# 23D_ESC_DRIVER.net
KiCad netlist of a schematic drawn in Altium Designer
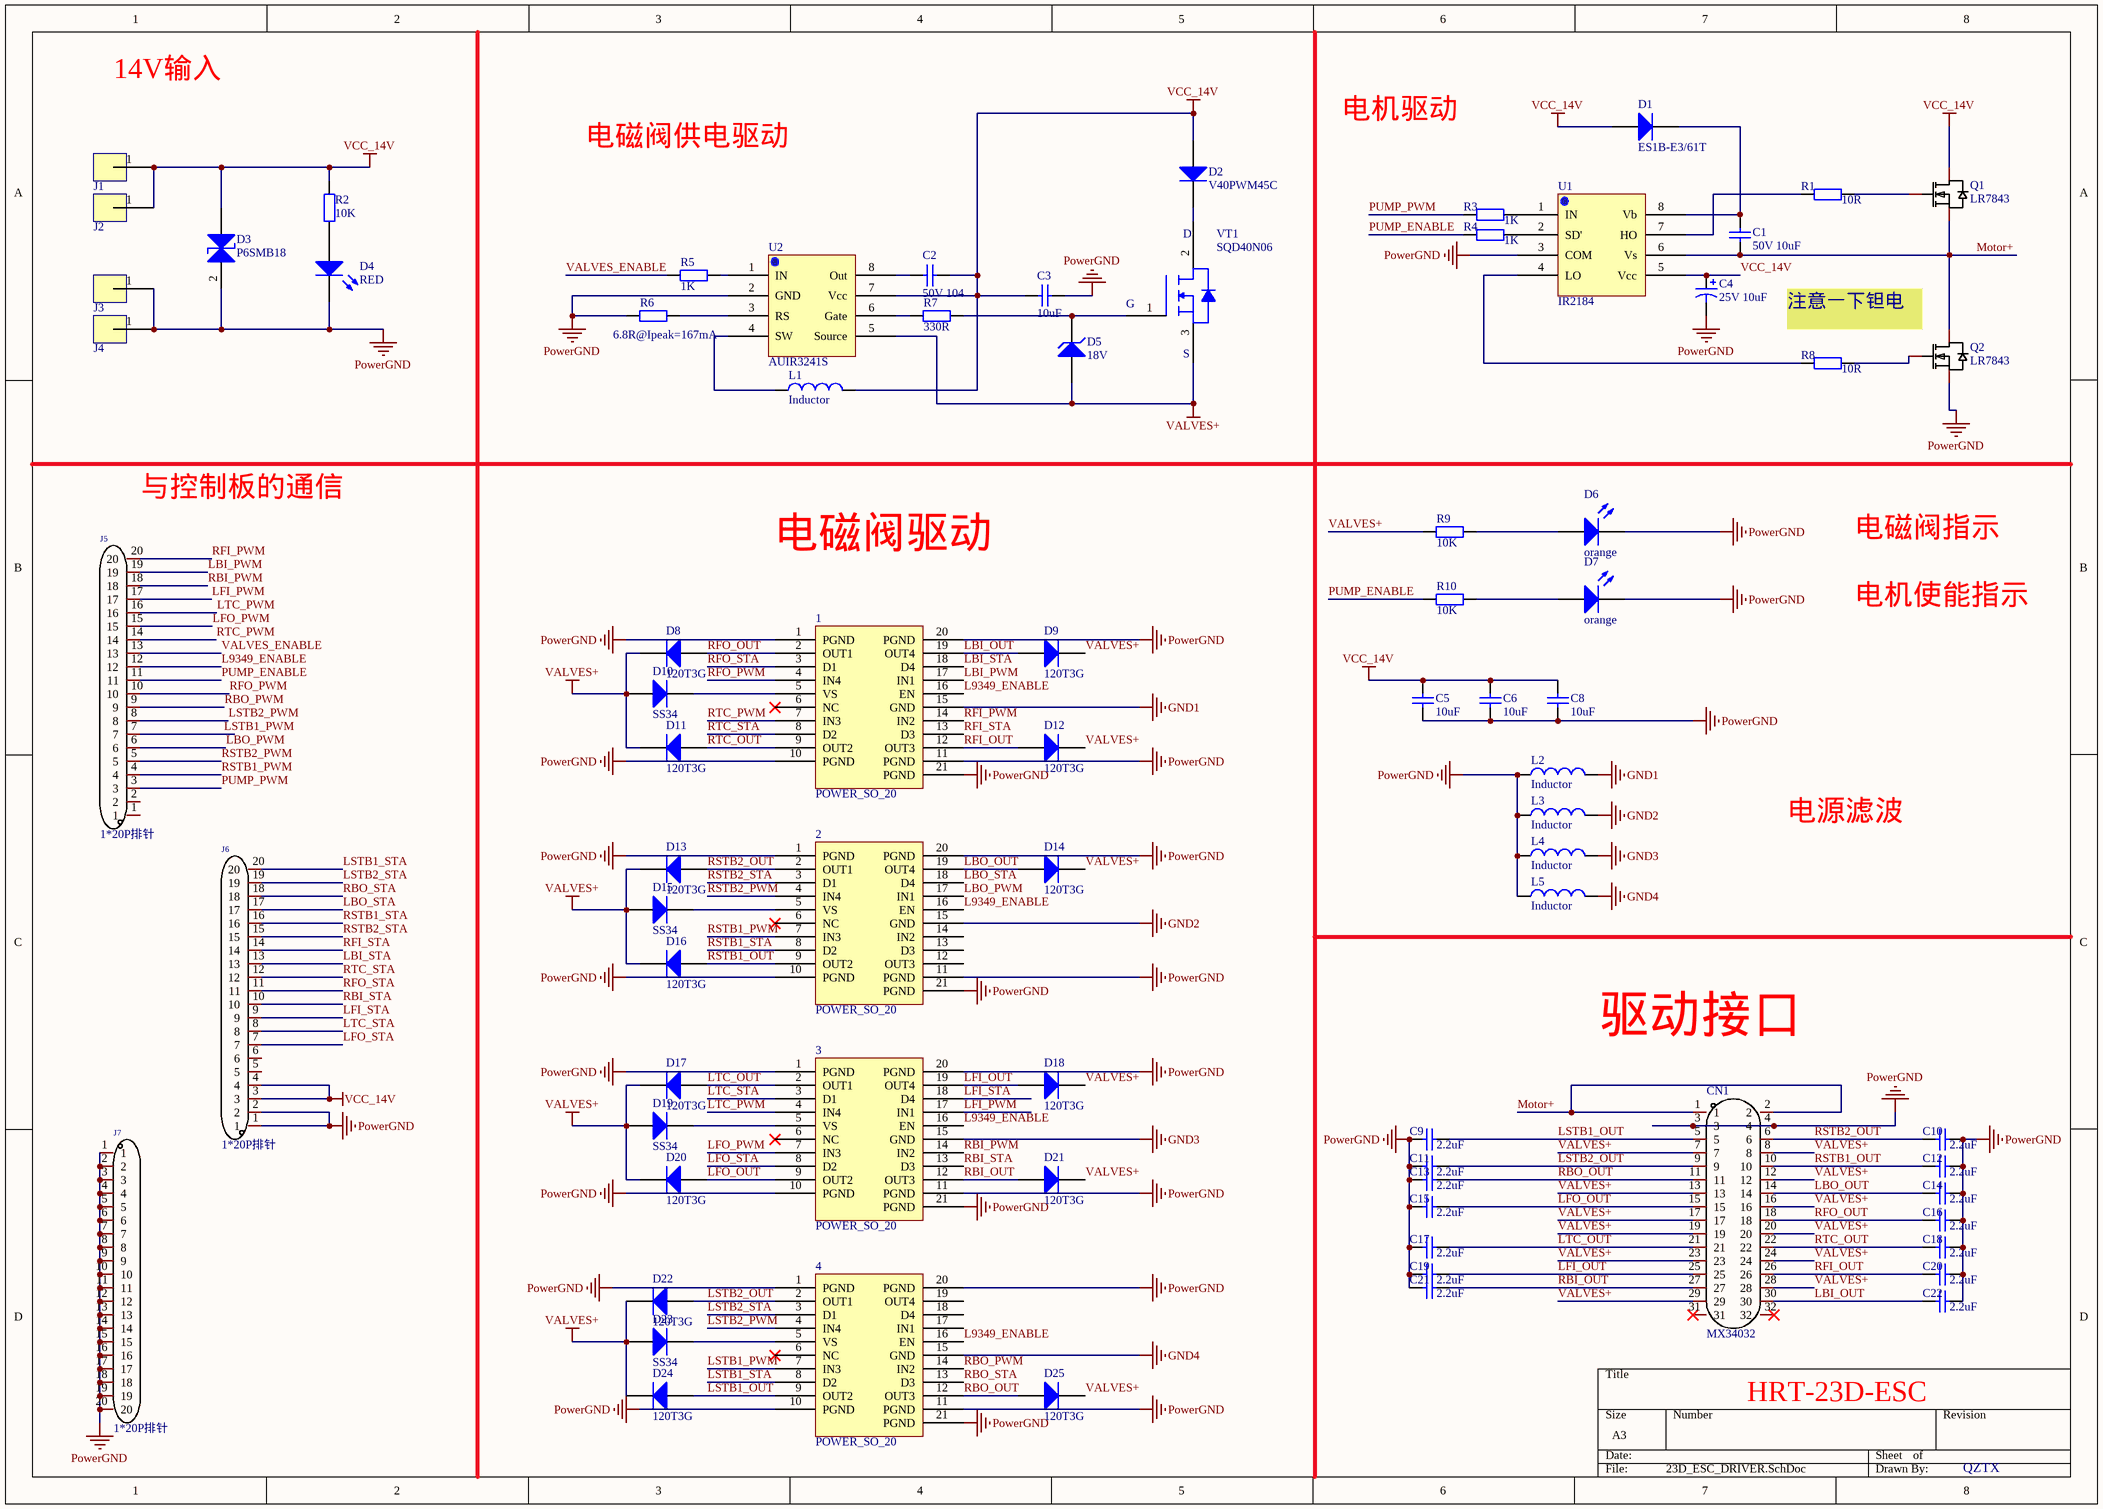
[diagram p0: 23D_ESC_DRIVER.SchDoc]

(export (version "E")
  (design (tool "Eeschema 10.0.6"))
  (components
    (comp (ref "1")
      (value "POWER_SO_20")
      (footprint "POWERSO-20_self_with3D_USEable:POWERSO-20_L15.9-W11.0-P1.27-LS14.2-BL-EP")
      (libsource (lib "PowerSO-20") (part "POWER_SO_20"))
    )
    (comp (ref "2")
      (value "POWER_SO_20")
      (footprint "POWERSO-20_self_with3D_USEable:POWERSO-20_L15.9-W11.0-P1.27-LS14.2-BL-EP")
      (libsource (lib "PowerSO-20") (part "POWER_SO_20"))
    )
    (comp (ref "3")
      (value "POWER_SO_20")
      (footprint "POWERSO-20_self_with3D_USEable:POWERSO-20_L15.9-W11.0-P1.27-LS14.2-BL-EP")
      (libsource (lib "PowerSO-20") (part "POWER_SO_20"))
    )
    (comp (ref "4")
      (value "POWER_SO_20")
      (footprint "POWERSO-20_self_with3D_USEable:POWERSO-20_L15.9-W11.0-P1.27-LS14.2-BL-EP")
      (libsource (lib "PowerSO-20") (part "POWER_SO_20"))
    )
    (comp (ref "C1")
      (value "50V 10uF")
      (footprint "C 0805")
      (description "无极性电容")
      (libsource (lib "HRT_D Schlib") (part "Cap"))
    )
    (comp (ref "C2")
      (value "50V 104")
      (footprint "C 0805")
      (description "无极性电容")
      (libsource (lib "HRT_D Schlib") (part "Cap"))
    )
    (comp (ref "C3")
      (value "10uF")
      (footprint "C 0805")
      (description "无极性电容")
      (libsource (lib "HRT_D Schlib") (part "Cap"))
    )
    (comp (ref "C4")
      (value "25V 10uF")
      (footprint "CP 3528B")
      (description "极性电容")
      (libsource (lib "ER100_ESC") (part "Cap_Pol"))
    )
    (comp (ref "C5")
      (value "10uF")
      (footprint "C 0805")
      (description "无极性电容")
      (libsource (lib "HRT_D Schlib") (part "Cap"))
    )
    (comp (ref "C6")
      (value "10uF")
      (footprint "C 0805")
      (description "无极性电容")
      (libsource (lib "HRT_D Schlib") (part "Cap"))
    )
    (comp (ref "C8")
      (value "10uF")
      (footprint "C 0805")
      (description "无极性电容")
      (libsource (lib "HRT_D Schlib") (part "Cap"))
    )
    (comp (ref "C9")
      (value "2.2uF")
      (footprint "C 0805")
      (description "无极性电容")
      (libsource (lib "HRT_D Schlib") (part "Cap"))
    )
    (comp (ref "C10")
      (value "2.2uF")
      (footprint "C 0805")
      (description "无极性电容")
      (libsource (lib "HRT_D Schlib") (part "Cap"))
    )
    (comp (ref "C11")
      (value "2.2uF")
      (footprint "C 0805")
      (description "无极性电容")
      (libsource (lib "HRT_D Schlib") (part "Cap"))
    )
    (comp (ref "C12")
      (value "2.2uF")
      (footprint "C 0805")
      (description "无极性电容")
      (libsource (lib "HRT_D Schlib") (part "Cap"))
    )
    (comp (ref "C13")
      (value "2.2uF")
      (footprint "C 0805")
      (description "无极性电容")
      (libsource (lib "HRT_D Schlib") (part "Cap"))
    )
    (comp (ref "C14")
      (value "2.2uF")
      (footprint "C 0805")
      (description "无极性电容")
      (libsource (lib "HRT_D Schlib") (part "Cap"))
    )
    (comp (ref "C15")
      (value "2.2uF")
      (footprint "C 0805")
      (description "无极性电容")
      (libsource (lib "HRT_D Schlib") (part "Cap"))
    )
    (comp (ref "C16")
      (value "2.2uF")
      (footprint "C 0805")
      (description "无极性电容")
      (libsource (lib "HRT_D Schlib") (part "Cap"))
    )
    (comp (ref "C17")
      (value "2.2uF")
      (footprint "C 0805")
      (description "无极性电容")
      (libsource (lib "HRT_D Schlib") (part "Cap"))
    )
    (comp (ref "C18")
      (value "2.2uF")
      (footprint "C 0805")
      (description "无极性电容")
      (libsource (lib "HRT_D Schlib") (part "Cap"))
    )
    (comp (ref "C19")
      (value "2.2uF")
      (footprint "C 0805")
      (description "无极性电容")
      (libsource (lib "HRT_D Schlib") (part "Cap"))
    )
    (comp (ref "C20")
      (value "2.2uF")
      (footprint "C 0805")
      (description "无极性电容")
      (libsource (lib "HRT_D Schlib") (part "Cap"))
    )
    (comp (ref "C21")
      (value "2.2uF")
      (footprint "C 0805")
      (description "无极性电容")
      (libsource (lib "HRT_D Schlib") (part "Cap"))
    )
    (comp (ref "C22")
      (value "2.2uF")
      (footprint "C 0805")
      (description "无极性电容")
      (libsource (lib "HRT_D Schlib") (part "Cap"))
    )
    (comp (ref "CN1")
      (value "MX34032NF2")
      (footprint "CONN-TH_MX34032NF2")
      (description "间距:2.2mm;插针结构:2x16P;排数:2;每排PIN数:16;行距:3mm;公母:公型插针;安装方式:弯插;")
      (fields (field (name "MANUFACTURER") "JAE(日本航空电子)") (field (name "NAME") "MX34032"))
      (libsource (lib "MX34032") (part "MX34032NF2"))
    )
    (comp (ref "D1")
      (value "ES1B-E3/61T")
      (footprint "DO-214")
      (description "二极管")
      (libsource (lib "ER100_ESC") (part "Diode"))
    )
    (comp (ref "D2")
      (value "V40PWM45C")
      (footprint "TO252_DIO")
      (description "二极管")
      (libsource (lib "ER100_ESC") (part "Diode"))
    )
    (comp (ref "D3")
      (value "P6SMB18")
      (footprint "DO-214AA")
      (description "BiDir TVS Diode")
      (libsource (lib "ER100_ESC") (part "P6SMBXX"))
    )
    (comp (ref "D4")
      (value "RED")
      (footprint "LED_0805")
      (description "发光二极管")
      (libsource (lib "ESC_control") (part "LED"))
    )
    (comp (ref "D5") (value "18V") (footprint "LL34") (libsource (lib "ER100_ESC") (part "Diode_Zener")))
    (comp (ref "D6")
      (value "orange")
      (footprint "LED_0805")
      (description "发光二极管")
      (libsource (lib "ESC_control") (part "LED"))
    )
    (comp (ref "D7")
      (value "orange")
      (footprint "LED_0805")
      (description "发光二极管")
      (libsource (lib "ESC_control") (part "LED"))
    )
    (comp (ref "D8")
      (value "120T3G")
      (footprint "DO-214")
      (description "二极管")
      (libsource (lib "ER100_ESC") (part "Diode"))
    )
    (comp (ref "D9")
      (value "120T3G")
      (footprint "DO-214")
      (description "二极管")
      (libsource (lib "ER100_ESC") (part "Diode"))
    )
    (comp (ref "D10")
      (value "SS34")
      (footprint "DO-214")
      (description "二极管")
      (libsource (lib "ESC_control") (part "Diode"))
    )
    (comp (ref "D11")
      (value "120T3G")
      (footprint "DO-214")
      (description "二极管")
      (libsource (lib "ER100_ESC") (part "Diode"))
    )
    (comp (ref "D12")
      (value "120T3G")
      (footprint "DO-214")
      (description "二极管")
      (libsource (lib "ER100_ESC") (part "Diode"))
    )
    (comp (ref "D13")
      (value "120T3G")
      (footprint "DO-214")
      (description "二极管")
      (libsource (lib "ER100_ESC") (part "Diode"))
    )
    (comp (ref "D14")
      (value "120T3G")
      (footprint "DO-214")
      (description "二极管")
      (libsource (lib "ER100_ESC") (part "Diode"))
    )
    (comp (ref "D15")
      (value "SS34")
      (footprint "DO-214")
      (description "二极管")
      (libsource (lib "ESC_control") (part "Diode"))
    )
    (comp (ref "D16")
      (value "120T3G")
      (footprint "DO-214")
      (description "二极管")
      (libsource (lib "ER100_ESC") (part "Diode"))
    )
    (comp (ref "D17")
      (value "120T3G")
      (footprint "DO-214")
      (description "二极管")
      (libsource (lib "ER100_ESC") (part "Diode"))
    )
    (comp (ref "D18")
      (value "120T3G")
      (footprint "DO-214")
      (description "二极管")
      (libsource (lib "ER100_ESC") (part "Diode"))
    )
    (comp (ref "D19")
      (value "SS34")
      (footprint "DO-214")
      (description "二极管")
      (libsource (lib "ESC_control") (part "Diode"))
    )
    (comp (ref "D20")
      (value "120T3G")
      (footprint "DO-214")
      (description "二极管")
      (libsource (lib "ER100_ESC") (part "Diode"))
    )
    (comp (ref "D21")
      (value "120T3G")
      (footprint "DO-214")
      (description "二极管")
      (libsource (lib "ER100_ESC") (part "Diode"))
    )
    (comp (ref "D22")
      (value "120T3G")
      (footprint "DO-214")
      (description "二极管")
      (libsource (lib "ER100_ESC") (part "Diode"))
    )
    (comp (ref "D23")
      (value "SS34")
      (footprint "DO-214")
      (description "二极管")
      (libsource (lib "ESC_control") (part "Diode"))
    )
    (comp (ref "D24")
      (value "120T3G")
      (footprint "DO-214")
      (description "二极管")
      (libsource (lib "ER100_ESC") (part "Diode"))
    )
    (comp (ref "D25")
      (value "120T3G")
      (footprint "DO-214")
      (description "二极管")
      (libsource (lib "ER100_ESC") (part "Diode"))
    )
    (comp (ref "J1")
      (value "SMT_Connector")
      (footprint "SMT_Connector")
      (description "表贴接线端")
      (libsource (lib "ER100_ESC") (part "SMT_Connector"))
    )
    (comp (ref "J2")
      (value "SMT_Connector")
      (footprint "SMT_Connector")
      (description "表贴接线端")
      (libsource (lib "ER100_ESC") (part "SMT_Connector"))
    )
    (comp (ref "J3")
      (value "SMT_Connector")
      (footprint "SMT_Connector")
      (description "表贴接线端")
      (libsource (lib "ER100_ESC") (part "SMT_Connector"))
    )
    (comp (ref "J4")
      (value "SMT_Connector")
      (footprint "SMT_Connector")
      (description "表贴接线端")
      (libsource (lib "ER100_ESC") (part "SMT_Connector"))
    )
    (comp (ref "J5")
      (value "2.54-1*20P直针")
      (footprint "HDR-TH_20P-P2.54-V-M-1")
      (fields (field (name "MANUFACTURER") "BOOMELE(博穆精密)") (field (name "NAME") "1*20P排针"))
      (libsource (lib "20P排针2.54mm") (part "2.54-1*20P直针"))
    )
    (comp (ref "J6")
      (value "2.54-1*20P直针")
      (footprint "HDR-TH_20P-P2.54-V-M-1")
      (fields (field (name "MANUFACTURER") "BOOMELE(博穆精密)") (field (name "NAME") "1*20P排针"))
      (libsource (lib "20P排针2.54mm") (part "2.54-1*20P直针"))
    )
    (comp (ref "J7")
      (value "2.54-1*20P直针")
      (footprint "HDR2.54-LI-20P")
      (fields (field (name "MANUFACTURER") "BOOMELE(博穆精密)") (field (name "NAME") "1*20P排针"))
      (libsource (lib "20P排针2.54mm") (part "2.54-1*20P直针"))
    )
    (comp (ref "L1")
      (value "Inductor")
      (footprint "L 0805")
      (description "电感")
      (libsource (lib "HRT_D Schlib") (part "Inductor"))
    )
    (comp (ref "L2")
      (value "Inductor")
      (footprint "L 0805")
      (description "电感")
      (libsource (lib "HRT_D Schlib") (part "Inductor"))
    )
    (comp (ref "L3")
      (value "Inductor")
      (footprint "L 0805")
      (description "电感")
      (libsource (lib "HRT_D Schlib") (part "Inductor"))
    )
    (comp (ref "L4")
      (value "Inductor")
      (footprint "L 0805")
      (description "电感")
      (libsource (lib "HRT_D Schlib") (part "Inductor"))
    )
    (comp (ref "L5")
      (value "Inductor")
      (footprint "L 0805")
      (description "电感")
      (libsource (lib "HRT_D Schlib") (part "Inductor"))
    )
    (comp (ref "Q1")
      (value "LR7843-VB")
      (footprint "TO-252-2_L6.6-W6.1-P4.58-LS9.9-BR")
      (description "类型:N沟道;漏源电压(Vdss):30V;连续漏极电流(Id):120A;导通电阻(RDS(on)@Vgs,Id):2.3mΩ@10V,120A;")
      (fields (field (name "MANUFACTURER") "VBsemi(微碧)") (field (name "NAME") "LR7843"))
      (libsource (lib "LR7843") (part "LR7843-VB"))
    )
    (comp (ref "Q2")
      (value "LR7843-VB")
      (footprint "TO-252-2_L6.6-W6.1-P4.58-LS9.9-BR")
      (description "类型:N沟道;漏源电压(Vdss):30V;连续漏极电流(Id):120A;导通电阻(RDS(on)@Vgs,Id):2.3mΩ@10V,120A;")
      (fields (field (name "MANUFACTURER") "VBsemi(微碧)") (field (name "NAME") "LR7843"))
      (libsource (lib "LR7843") (part "LR7843-VB"))
    )
    (comp (ref "R1")
      (value "10R")
      (footprint "R 0805")
      (description "电阻")
      (libsource (lib "") (part "Resistor_1"))
    )
    (comp (ref "R2")
      (value "10K")
      (footprint "R 0805")
      (description "电阻")
      (libsource (lib "HRT_D Schlib") (part "Resistor"))
    )
    (comp (ref "R3")
      (value "1K")
      (footprint "R 0805")
      (description "电阻")
      (libsource (lib "") (part "Resistor_1"))
    )
    (comp (ref "R4")
      (value "1K")
      (footprint "R 0805")
      (description "电阻")
      (libsource (lib "") (part "Resistor_1"))
    )
    (comp (ref "R5")
      (value "1K")
      (footprint "R 0805")
      (description "电阻")
      (libsource (lib "") (part "Resistor_1"))
    )
    (comp (ref "R6")
      (value "6.8R@Ipeak=167mA")
      (footprint "R 0805")
      (description "电阻")
      (libsource (lib "") (part "Resistor_1"))
    )
    (comp (ref "R7")
      (value "330R")
      (footprint "R 0805")
      (description "电阻")
      (libsource (lib "") (part "Resistor_1"))
    )
    (comp (ref "R8")
      (value "10R")
      (footprint "R 0805")
      (description "电阻")
      (libsource (lib "") (part "Resistor_1"))
    )
    (comp (ref "R9")
      (value "10K")
      (footprint "R 0805")
      (description "电阻")
      (libsource (lib "") (part "Resistor_1"))
    )
    (comp (ref "R10")
      (value "10K")
      (footprint "R 0805")
      (description "电阻")
      (libsource (lib "") (part "Resistor_1"))
    )
    (comp (ref "U1")
      (value "IR2184")
      (footprint "SOP8")
      (description "Half-Bridge Gate Driver")
      (libsource (lib "ER100_ESC") (part "IR2184"))
    )
    (comp (ref "U2")
      (value "AUIR3241S")
      (footprint "SOP8")
      (description "B2B MOSFET Driver")
      (libsource (lib "ER100_ESC") (part "AUIR3241S"))
    )
    (comp (ref "VT1")
      (value "SQD40N06")
      (footprint "TO252")
      (libsource (lib "ER100_ESC") (part "PowerMos_N"))
    )
  )
  (nets
    (net (code "1") (name "/L9349_ENABLE") (class "Default")
      (node (ref "1") (pin "16") (pinfunction "EN_16") (pintype "passive"))
      (node (ref "2") (pin "16") (pinfunction "EN_16") (pintype "passive"))
      (node (ref "3") (pin "16") (pinfunction "EN_16") (pintype "passive"))
      (node (ref "4") (pin "16") (pinfunction "EN_16") (pintype "passive"))
      (node (ref "J5") (pin "12") (pinfunction "12_12") (pintype "passive"))
    )
    (net (code "2") (name "/LBI_OUT") (class "Default")
      (node (ref "1") (pin "19") (pinfunction "OUT4_19") (pintype "passive"))
      (node (ref "C22") (pin "1") (pinfunction "1_1") (pintype "passive"))
      (node (ref "CN1") (pin "30") (pinfunction "30_30") (pintype "passive"))
      (node (ref "D9") (pin "1") (pinfunction "A_1") (pintype "passive"))
    )
    (net (code "3") (name "/LBI_PWM") (class "Default")
      (node (ref "1") (pin "17") (pinfunction "IN1_17") (pintype "passive"))
      (node (ref "J5") (pin "19") (pinfunction "19_19") (pintype "passive"))
    )
    (net (code "4") (name "/LBI_STA") (class "Default")
      (node (ref "1") (pin "18") (pinfunction "D4_18") (pintype "passive"))
      (node (ref "J6") (pin "13") (pinfunction "13_13") (pintype "passive"))
    )
    (net (code "5") (name "/LBO_OUT") (class "Default")
      (node (ref "2") (pin "19") (pinfunction "OUT4_19") (pintype "passive"))
      (node (ref "C14") (pin "1") (pinfunction "1_1") (pintype "passive"))
      (node (ref "CN1") (pin "14") (pinfunction "14_14") (pintype "passive"))
      (node (ref "D14") (pin "1") (pinfunction "A_1") (pintype "passive"))
    )
    (net (code "6") (name "/LBO_PWM") (class "Default")
      (node (ref "2") (pin "17") (pinfunction "IN1_17") (pintype "passive"))
      (node (ref "J5") (pin "6") (pinfunction "6_6") (pintype "passive"))
    )
    (net (code "7") (name "/LBO_STA") (class "Default")
      (node (ref "2") (pin "18") (pinfunction "D4_18") (pintype "passive"))
      (node (ref "J6") (pin "17") (pinfunction "17_17") (pintype "passive"))
    )
    (net (code "8") (name "/LFI_OUT") (class "Default")
      (node (ref "3") (pin "19") (pinfunction "OUT4_19") (pintype "passive"))
      (node (ref "C19") (pin "2") (pinfunction "2_2") (pintype "passive"))
      (node (ref "CN1") (pin "25") (pinfunction "25_25") (pintype "passive"))
      (node (ref "D18") (pin "1") (pinfunction "A_1") (pintype "passive"))
    )
    (net (code "9") (name "/LFI_PWM") (class "Default")
      (node (ref "3") (pin "17") (pinfunction "IN1_17") (pintype "passive"))
      (node (ref "J5") (pin "17") (pinfunction "17_17") (pintype "passive"))
    )
    (net (code "10") (name "/LFI_STA") (class "Default")
      (node (ref "3") (pin "18") (pinfunction "D4_18") (pintype "passive"))
      (node (ref "J6") (pin "9") (pinfunction "9_9") (pintype "passive"))
    )
    (net (code "11") (name "/LFO_OUT") (class "Default")
      (node (ref "3") (pin "9") (pinfunction "OUT2_9") (pintype "passive"))
      (node (ref "C15") (pin "2") (pinfunction "2_2") (pintype "passive"))
      (node (ref "CN1") (pin "15") (pinfunction "15_15") (pintype "passive"))
      (node (ref "D20") (pin "1") (pinfunction "A_1") (pintype "passive"))
    )
    (net (code "12") (name "/LFO_PWM") (class "Default")
      (node (ref "3") (pin "7") (pinfunction "IN3_7") (pintype "passive"))
      (node (ref "J5") (pin "15") (pinfunction "15_15") (pintype "passive"))
    )
    (net (code "13") (name "/LFO_STA") (class "Default")
      (node (ref "3") (pin "8") (pinfunction "D2_8") (pintype "passive"))
      (node (ref "J6") (pin "7") (pinfunction "7_7") (pintype "passive"))
    )
    (net (code "14") (name "/LSTB1_OUT") (class "Default")
      (node (ref "4") (pin "9") (pinfunction "OUT2_9") (pintype "passive"))
      (node (ref "C9") (pin "2") (pinfunction "2_2") (pintype "passive"))
      (node (ref "CN1") (pin "5") (pinfunction "5_5") (pintype "passive"))
      (node (ref "D24") (pin "1") (pinfunction "A_1") (pintype "passive"))
    )
    (net (code "15") (name "/LSTB1_PWM") (class "Default")
      (node (ref "4") (pin "7") (pinfunction "IN3_7") (pintype "passive"))
      (node (ref "J5") (pin "7") (pinfunction "7_7") (pintype "passive"))
    )
    (net (code "16") (name "/LSTB1_STA") (class "Default")
      (node (ref "4") (pin "8") (pinfunction "D2_8") (pintype "passive"))
      (node (ref "J6") (pin "20") (pinfunction "20_20") (pintype "passive"))
    )
    (net (code "17") (name "/LSTB2_OUT") (class "Default")
      (node (ref "4") (pin "2") (pinfunction "OUT1_2") (pintype "passive"))
      (node (ref "C11") (pin "2") (pinfunction "2_2") (pintype "passive"))
      (node (ref "CN1") (pin "9") (pinfunction "9_9") (pintype "passive"))
      (node (ref "D22") (pin "1") (pinfunction "A_1") (pintype "passive"))
    )
    (net (code "18") (name "/LSTB2_PWM") (class "Default")
      (node (ref "4") (pin "4") (pinfunction "IN4_4") (pintype "passive"))
      (node (ref "J5") (pin "8") (pinfunction "8_8") (pintype "passive"))
    )
    (net (code "19") (name "/LSTB2_STA") (class "Default")
      (node (ref "4") (pin "3") (pinfunction "D1_3") (pintype "passive"))
      (node (ref "J6") (pin "19") (pinfunction "19_19") (pintype "passive"))
    )
    (net (code "20") (name "/LTC_OUT") (class "Default")
      (node (ref "3") (pin "2") (pinfunction "OUT1_2") (pintype "passive"))
      (node (ref "C17") (pin "2") (pinfunction "2_2") (pintype "passive"))
      (node (ref "CN1") (pin "21") (pinfunction "21_21") (pintype "passive"))
      (node (ref "D17") (pin "1") (pinfunction "A_1") (pintype "passive"))
    )
    (net (code "21") (name "/LTC_PWM") (class "Default")
      (node (ref "3") (pin "4") (pinfunction "IN4_4") (pintype "passive"))
      (node (ref "J5") (pin "16") (pinfunction "16_16") (pintype "passive"))
    )
    (net (code "22") (name "/LTC_STA") (class "Default")
      (node (ref "3") (pin "3") (pinfunction "D1_3") (pintype "passive"))
      (node (ref "J6") (pin "8") (pinfunction "8_8") (pintype "passive"))
    )
    (net (code "23") (name "/Motor+") (class "Default")
      (node (ref "C1") (pin "1") (pinfunction "1_1") (pintype "passive"))
      (node (ref "CN1") (pin "1") (pinfunction "1_1") (pintype "passive"))
      (node (ref "CN1") (pin "2") (pinfunction "2_2") (pintype "passive"))
      (node (ref "Q1") (pin "3") (pinfunction "S_3") (pintype "passive"))
      (node (ref "Q2") (pin "2") (pinfunction "D_2") (pintype "passive"))
      (node (ref "U1") (pin "6") (pinfunction "Vs_6") (pintype "passive"))
    )
    (net (code "24") (name "/PUMP_ENABLE") (class "Default")
      (node (ref "J5") (pin "11") (pinfunction "11_11") (pintype "passive"))
      (node (ref "R10") (pin "1") (pinfunction "1_1") (pintype "passive"))
      (node (ref "R4") (pin "1") (pinfunction "1_1") (pintype "passive"))
    )
    (net (code "25") (name "/PUMP_PWM") (class "Default")
      (node (ref "J5") (pin "3") (pinfunction "3_3") (pintype "passive"))
      (node (ref "R3") (pin "1") (pinfunction "1_1") (pintype "passive"))
    )
    (net (code "26") (name "/RBI_OUT") (class "Default")
      (node (ref "3") (pin "12") (pinfunction "OUT3_12") (pintype "passive"))
      (node (ref "C21") (pin "2") (pinfunction "2_2") (pintype "passive"))
      (node (ref "CN1") (pin "27") (pinfunction "27_27") (pintype "passive"))
      (node (ref "D21") (pin "1") (pinfunction "A_1") (pintype "passive"))
    )
    (net (code "27") (name "/RBI_PWM") (class "Default")
      (node (ref "3") (pin "14") (pinfunction "IN2_14") (pintype "passive"))
      (node (ref "J5") (pin "18") (pinfunction "18_18") (pintype "passive"))
    )
    (net (code "28") (name "/RBI_STA") (class "Default")
      (node (ref "3") (pin "13") (pinfunction "D3_13") (pintype "passive"))
      (node (ref "J6") (pin "10") (pinfunction "10_10") (pintype "passive"))
    )
    (net (code "29") (name "/RBO_OUT") (class "Default")
      (node (ref "4") (pin "12") (pinfunction "OUT3_12") (pintype "passive"))
      (node (ref "C13") (pin "2") (pinfunction "2_2") (pintype "passive"))
      (node (ref "CN1") (pin "11") (pinfunction "11_11") (pintype "passive"))
      (node (ref "D25") (pin "1") (pinfunction "A_1") (pintype "passive"))
    )
    (net (code "30") (name "/RBO_PWM") (class "Default")
      (node (ref "4") (pin "14") (pinfunction "IN2_14") (pintype "passive"))
      (node (ref "J5") (pin "9") (pinfunction "9_9") (pintype "passive"))
    )
    (net (code "31") (name "/RBO_STA") (class "Default")
      (node (ref "4") (pin "13") (pinfunction "D3_13") (pintype "passive"))
      (node (ref "J6") (pin "18") (pinfunction "18_18") (pintype "passive"))
    )
    (net (code "32") (name "/RFI_OUT") (class "Default")
      (node (ref "1") (pin "12") (pinfunction "OUT3_12") (pintype "passive"))
      (node (ref "C20") (pin "1") (pinfunction "1_1") (pintype "passive"))
      (node (ref "CN1") (pin "26") (pinfunction "26_26") (pintype "passive"))
      (node (ref "D12") (pin "1") (pinfunction "A_1") (pintype "passive"))
    )
    (net (code "33") (name "/RFI_PWM") (class "Default")
      (node (ref "1") (pin "14") (pinfunction "IN2_14") (pintype "passive"))
      (node (ref "J5") (pin "20") (pinfunction "20_20") (pintype "passive"))
    )
    (net (code "34") (name "/RFI_STA") (class "Default")
      (node (ref "1") (pin "13") (pinfunction "D3_13") (pintype "passive"))
      (node (ref "J6") (pin "14") (pinfunction "14_14") (pintype "passive"))
    )
    (net (code "35") (name "/RFO_OUT") (class "Default")
      (node (ref "1") (pin "2") (pinfunction "OUT1_2") (pintype "passive"))
      (node (ref "C16") (pin "1") (pinfunction "1_1") (pintype "passive"))
      (node (ref "CN1") (pin "18") (pinfunction "18_18") (pintype "passive"))
      (node (ref "D8") (pin "1") (pinfunction "A_1") (pintype "passive"))
    )
    (net (code "36") (name "/RFO_PWM") (class "Default")
      (node (ref "1") (pin "4") (pinfunction "IN4_4") (pintype "passive"))
      (node (ref "J5") (pin "10") (pinfunction "10_10") (pintype "passive"))
    )
    (net (code "37") (name "/RFO_STA") (class "Default")
      (node (ref "1") (pin "3") (pinfunction "D1_3") (pintype "passive"))
      (node (ref "J6") (pin "11") (pinfunction "11_11") (pintype "passive"))
    )
    (net (code "38") (name "/RSTB1_OUT") (class "Default")
      (node (ref "2") (pin "9") (pinfunction "OUT2_9") (pintype "passive"))
      (node (ref "C12") (pin "1") (pinfunction "1_1") (pintype "passive"))
      (node (ref "CN1") (pin "10") (pinfunction "10_10") (pintype "passive"))
      (node (ref "D16") (pin "1") (pinfunction "A_1") (pintype "passive"))
    )
    (net (code "39") (name "/RSTB1_PWM") (class "Default")
      (node (ref "2") (pin "7") (pinfunction "IN3_7") (pintype "passive"))
      (node (ref "J5") (pin "4") (pinfunction "4_4") (pintype "passive"))
    )
    (net (code "40") (name "/RSTB1_STA") (class "Default")
      (node (ref "2") (pin "8") (pinfunction "D2_8") (pintype "passive"))
      (node (ref "J6") (pin "16") (pinfunction "16_16") (pintype "passive"))
    )
    (net (code "41") (name "/RSTB2_OUT") (class "Default")
      (node (ref "2") (pin "2") (pinfunction "OUT1_2") (pintype "passive"))
      (node (ref "C10") (pin "1") (pinfunction "1_1") (pintype "passive"))
      (node (ref "CN1") (pin "6") (pinfunction "6_6") (pintype "passive"))
      (node (ref "D13") (pin "1") (pinfunction "A_1") (pintype "passive"))
    )
    (net (code "42") (name "/RSTB2_PWM") (class "Default")
      (node (ref "2") (pin "4") (pinfunction "IN4_4") (pintype "passive"))
      (node (ref "J5") (pin "5") (pinfunction "5_5") (pintype "passive"))
    )
    (net (code "43") (name "/RSTB2_STA") (class "Default")
      (node (ref "2") (pin "3") (pinfunction "D1_3") (pintype "passive"))
      (node (ref "J6") (pin "15") (pinfunction "15_15") (pintype "passive"))
    )
    (net (code "44") (name "/RTC_OUT") (class "Default")
      (node (ref "1") (pin "9") (pinfunction "OUT2_9") (pintype "passive"))
      (node (ref "C18") (pin "1") (pinfunction "1_1") (pintype "passive"))
      (node (ref "CN1") (pin "22") (pinfunction "22_22") (pintype "passive"))
      (node (ref "D11") (pin "1") (pinfunction "A_1") (pintype "passive"))
    )
    (net (code "45") (name "/RTC_PWM") (class "Default")
      (node (ref "1") (pin "7") (pinfunction "IN3_7") (pintype "passive"))
      (node (ref "J5") (pin "14") (pinfunction "14_14") (pintype "passive"))
    )
    (net (code "46") (name "/RTC_STA") (class "Default")
      (node (ref "1") (pin "8") (pinfunction "D2_8") (pintype "passive"))
      (node (ref "J6") (pin "12") (pinfunction "12_12") (pintype "passive"))
    )
    (net (code "47") (name "/VALVES_ENABLE") (class "Default")
      (node (ref "J5") (pin "13") (pinfunction "13_13") (pintype "passive"))
      (node (ref "R5") (pin "1") (pinfunction "1_1") (pintype "passive"))
    )
    (net (code "48") (name "GND1") (class "Default")
      (node (ref "1") (pin "15") (pinfunction "GND_15") (pintype "passive"))
      (node (ref "L2") (pin "2") (pinfunction "2_2") (pintype "passive"))
    )
    (net (code "49") (name "GND2") (class "Default")
      (node (ref "2") (pin "15") (pinfunction "GND_15") (pintype "passive"))
      (node (ref "L3") (pin "2") (pinfunction "2_2") (pintype "passive"))
    )
    (net (code "50") (name "GND3") (class "Default")
      (node (ref "3") (pin "15") (pinfunction "GND_15") (pintype "passive"))
      (node (ref "L4") (pin "2") (pinfunction "2_2") (pintype "passive"))
    )
    (net (code "51") (name "GND4") (class "Default")
      (node (ref "4") (pin "15") (pinfunction "GND_15") (pintype "passive"))
      (node (ref "L5") (pin "2") (pinfunction "2_2") (pintype "passive"))
    )
    (net (code "52") (name "Net-(1-VS)") (class "Default")
      (node (ref "1") (pin "5") (pinfunction "VS_5") (pintype "passive"))
      (node (ref "D10") (pin "2") (pinfunction "K_2") (pintype "passive"))
    )
    (net (code "53") (name "Net-(2-VS)") (class "Default")
      (node (ref "2") (pin "5") (pinfunction "VS_5") (pintype "passive"))
      (node (ref "D15") (pin "2") (pinfunction "K_2") (pintype "passive"))
    )
    (net (code "54") (name "Net-(3-VS)") (class "Default")
      (node (ref "3") (pin "5") (pinfunction "VS_5") (pintype "passive"))
      (node (ref "D19") (pin "2") (pinfunction "K_2") (pintype "passive"))
    )
    (net (code "55") (name "Net-(4-VS)") (class "Default")
      (node (ref "4") (pin "5") (pinfunction "VS_5") (pintype "passive"))
      (node (ref "D23") (pin "2") (pinfunction "K_2") (pintype "passive"))
    )
    (net (code "56") (name "Net-(D1-K)") (class "Default")
      (node (ref "C1") (pin "2") (pinfunction "2_2") (pintype "passive"))
      (node (ref "D1") (pin "2") (pinfunction "K_2") (pintype "passive"))
      (node (ref "U1") (pin "8") (pinfunction "Vb_8") (pintype "passive"))
    )
    (net (code "57") (name "Net-(D2-K)") (class "Default")
      (node (ref "D2") (pin "2") (pinfunction "K_2") (pintype "passive"))
      (node (ref "VT1") (pin "2") (pinfunction "2_2") (pintype "passive"))
    )
    (net (code "58") (name "Net-(D4-A)") (class "Default")
      (node (ref "D4") (pin "1") (pinfunction "A_1") (pintype "passive"))
      (node (ref "R2") (pin "1") (pinfunction "1_1") (pintype "passive"))
    )
    (net (code "59") (name "Net-(D5-K)") (class "Default")
      (node (ref "D5") (pin "2") (pinfunction "K_2") (pintype "passive"))
      (node (ref "R7") (pin "2") (pinfunction "2_2") (pintype "passive"))
      (node (ref "VT1") (pin "1") (pinfunction "G_1") (pintype "passive"))
    )
    (net (code "60") (name "Net-(D6-A)") (class "Default")
      (node (ref "D6") (pin "1") (pinfunction "A_1") (pintype "passive"))
      (node (ref "R9") (pin "2") (pinfunction "2_2") (pintype "passive"))
    )
    (net (code "61") (name "Net-(D7-A)") (class "Default")
      (node (ref "D7") (pin "1") (pinfunction "A_1") (pintype "passive"))
      (node (ref "R10") (pin "2") (pinfunction "2_2") (pintype "passive"))
    )
    (net (code "62") (name "Net-(Q1-G)") (class "Default")
      (node (ref "Q1") (pin "1") (pinfunction "G_1") (pintype "passive"))
      (node (ref "R1") (pin "2") (pinfunction "2_2") (pintype "passive"))
    )
    (net (code "63") (name "Net-(Q2-G)") (class "Default")
      (node (ref "Q2") (pin "1") (pinfunction "G_1") (pintype "passive"))
      (node (ref "R8") (pin "2") (pinfunction "2_2") (pintype "passive"))
    )
    (net (code "64") (name "Net-(U1-HO)") (class "Default")
      (node (ref "R1") (pin "1") (pinfunction "1_1") (pintype "passive"))
      (node (ref "U1") (pin "7") (pinfunction "HO_7") (pintype "passive"))
    )
    (net (code "65") (name "Net-(U1-IN)") (class "Default")
      (node (ref "R3") (pin "2") (pinfunction "2_2") (pintype "passive"))
      (node (ref "U1") (pin "1") (pinfunction "IN_1") (pintype "passive"))
    )
    (net (code "66") (name "Net-(U1-LO)") (class "Default")
      (node (ref "R8") (pin "1") (pinfunction "1_1") (pintype "passive"))
      (node (ref "U1") (pin "4") (pinfunction "LO_4") (pintype "passive"))
    )
    (net (code "67") (name "Net-(U1-SD')") (class "Default")
      (node (ref "R4") (pin "2") (pinfunction "2_2") (pintype "passive"))
      (node (ref "U1") (pin "2") (pinfunction "SD'_2") (pintype "passive"))
    )
    (net (code "68") (name "Net-(U2-Gate)") (class "Default")
      (node (ref "R7") (pin "1") (pinfunction "1_1") (pintype "passive"))
      (node (ref "U2") (pin "6") (pinfunction "Gate_6") (pintype "passive"))
    )
    (net (code "69") (name "Net-(U2-IN)") (class "Default")
      (node (ref "R5") (pin "2") (pinfunction "2_2") (pintype "passive"))
      (node (ref "U2") (pin "1") (pinfunction "IN_1") (pintype "passive"))
    )
    (net (code "70") (name "Net-(U2-Out)") (class "Default")
      (node (ref "C2") (pin "1") (pinfunction "1_1") (pintype "passive"))
      (node (ref "U2") (pin "8") (pinfunction "Out_8") (pintype "passive"))
    )
    (net (code "71") (name "Net-(U2-RS)") (class "Default")
      (node (ref "R6") (pin "2") (pinfunction "2_2") (pintype "passive"))
      (node (ref "U2") (pin "3") (pinfunction "RS_3") (pintype "passive"))
    )
    (net (code "72") (name "Net-(U2-SW)") (class "Default")
      (node (ref "L1") (pin "1") (pinfunction "1_1") (pintype "passive"))
      (node (ref "U2") (pin "4") (pinfunction "SW_4") (pintype "passive"))
    )
    (net (code "73") (name "PowerGND") (class "Default")
      (node (ref "1") (pin "1") (pinfunction "PGND_1") (pintype "passive"))
      (node (ref "1") (pin "10") (pinfunction "PGND_10") (pintype "passive"))
      (node (ref "1") (pin "11") (pinfunction "PGND_11") (pintype "passive"))
      (node (ref "1") (pin "20") (pinfunction "PGND_20") (pintype "passive"))
      (node (ref "1") (pin "21") (pinfunction "PGND_21") (pintype "passive"))
      (node (ref "2") (pin "1") (pinfunction "PGND_1") (pintype "passive"))
      (node (ref "2") (pin "10") (pinfunction "PGND_10") (pintype "passive"))
      (node (ref "2") (pin "11") (pinfunction "PGND_11") (pintype "passive"))
      (node (ref "2") (pin "20") (pinfunction "PGND_20") (pintype "passive"))
      (node (ref "2") (pin "21") (pinfunction "PGND_21") (pintype "passive"))
      (node (ref "3") (pin "1") (pinfunction "PGND_1") (pintype "passive"))
      (node (ref "3") (pin "10") (pinfunction "PGND_10") (pintype "passive"))
      (node (ref "3") (pin "11") (pinfunction "PGND_11") (pintype "passive"))
      (node (ref "3") (pin "20") (pinfunction "PGND_20") (pintype "passive"))
      (node (ref "3") (pin "21") (pinfunction "PGND_21") (pintype "passive"))
      (node (ref "4") (pin "1") (pinfunction "PGND_1") (pintype "passive"))
      (node (ref "4") (pin "10") (pinfunction "PGND_10") (pintype "passive"))
      (node (ref "4") (pin "11") (pinfunction "PGND_11") (pintype "passive"))
      (node (ref "4") (pin "20") (pinfunction "PGND_20") (pintype "passive"))
      (node (ref "4") (pin "21") (pinfunction "PGND_21") (pintype "passive"))
      (node (ref "C10") (pin "2") (pinfunction "2_2") (pintype "passive"))
      (node (ref "C11") (pin "1") (pinfunction "1_1") (pintype "passive"))
      (node (ref "C12") (pin "2") (pinfunction "2_2") (pintype "passive"))
      (node (ref "C13") (pin "1") (pinfunction "1_1") (pintype "passive"))
      (node (ref "C14") (pin "2") (pinfunction "2_2") (pintype "passive"))
      (node (ref "C15") (pin "1") (pinfunction "1_1") (pintype "passive"))
      (node (ref "C16") (pin "2") (pinfunction "2_2") (pintype "passive"))
      (node (ref "C17") (pin "1") (pinfunction "1_1") (pintype "passive"))
      (node (ref "C18") (pin "2") (pinfunction "2_2") (pintype "passive"))
      (node (ref "C19") (pin "1") (pinfunction "1_1") (pintype "passive"))
      (node (ref "C20") (pin "2") (pinfunction "2_2") (pintype "passive"))
      (node (ref "C21") (pin "1") (pinfunction "1_1") (pintype "passive"))
      (node (ref "C22") (pin "2") (pinfunction "2_2") (pintype "passive"))
      (node (ref "C3") (pin "2") (pinfunction "2_2") (pintype "passive"))
      (node (ref "C4") (pin "2") (pinfunction "2_2") (pintype "passive"))
      (node (ref "C5") (pin "1") (pinfunction "1_1") (pintype "passive"))
      (node (ref "C6") (pin "1") (pinfunction "1_1") (pintype "passive"))
      (node (ref "C8") (pin "1") (pinfunction "1_1") (pintype "passive"))
      (node (ref "C9") (pin "1") (pinfunction "1_1") (pintype "passive"))
      (node (ref "CN1") (pin "3") (pinfunction "3_3") (pintype "passive"))
      (node (ref "CN1") (pin "4") (pinfunction "4_4") (pintype "passive"))
      (node (ref "D3") (pin "2") (pinfunction "K_2") (pintype "passive"))
      (node (ref "D4") (pin "2") (pinfunction "K_2") (pintype "passive"))
      (node (ref "D6") (pin "2") (pinfunction "K_2") (pintype "passive"))
      (node (ref "D7") (pin "2") (pinfunction "K_2") (pintype "passive"))
      (node (ref "J3") (pin "1") (pinfunction "1_1") (pintype "passive"))
      (node (ref "J4") (pin "1") (pinfunction "1_1") (pintype "passive"))
      (node (ref "J6") (pin "1") (pinfunction "1_1") (pintype "passive"))
      (node (ref "J6") (pin "2") (pinfunction "2_2") (pintype "passive"))
      (node (ref "J7") (pin "1") (pinfunction "1_1") (pintype "passive"))
      (node (ref "J7") (pin "10") (pinfunction "10_10") (pintype "passive"))
      (node (ref "J7") (pin "11") (pinfunction "11_11") (pintype "passive"))
      (node (ref "J7") (pin "12") (pinfunction "12_12") (pintype "passive"))
      (node (ref "J7") (pin "13") (pinfunction "13_13") (pintype "passive"))
      (node (ref "J7") (pin "14") (pinfunction "14_14") (pintype "passive"))
      (node (ref "J7") (pin "15") (pinfunction "15_15") (pintype "passive"))
      (node (ref "J7") (pin "16") (pinfunction "16_16") (pintype "passive"))
      (node (ref "J7") (pin "17") (pinfunction "17_17") (pintype "passive"))
      (node (ref "J7") (pin "18") (pinfunction "18_18") (pintype "passive"))
      (node (ref "J7") (pin "19") (pinfunction "19_19") (pintype "passive"))
      (node (ref "J7") (pin "2") (pinfunction "2_2") (pintype "passive"))
      (node (ref "J7") (pin "20") (pinfunction "20_20") (pintype "passive"))
      (node (ref "J7") (pin "3") (pinfunction "3_3") (pintype "passive"))
      (node (ref "J7") (pin "4") (pinfunction "4_4") (pintype "passive"))
      (node (ref "J7") (pin "5") (pinfunction "5_5") (pintype "passive"))
      (node (ref "J7") (pin "6") (pinfunction "6_6") (pintype "passive"))
      (node (ref "J7") (pin "7") (pinfunction "7_7") (pintype "passive"))
      (node (ref "J7") (pin "8") (pinfunction "8_8") (pintype "passive"))
      (node (ref "J7") (pin "9") (pinfunction "9_9") (pintype "passive"))
      (node (ref "L2") (pin "1") (pinfunction "1_1") (pintype "passive"))
      (node (ref "L3") (pin "1") (pinfunction "1_1") (pintype "passive"))
      (node (ref "L4") (pin "1") (pinfunction "1_1") (pintype "passive"))
      (node (ref "L5") (pin "1") (pinfunction "1_1") (pintype "passive"))
      (node (ref "Q2") (pin "3") (pinfunction "S_3") (pintype "passive"))
      (node (ref "R6") (pin "1") (pinfunction "1_1") (pintype "passive"))
      (node (ref "U1") (pin "3") (pinfunction "COM_3") (pintype "passive"))
      (node (ref "U2") (pin "2") (pinfunction "GND_2") (pintype "passive"))
    )
    (net (code "74") (name "VALVES+") (class "Default")
      (node (ref "CN1") (pin "12") (pinfunction "12_12") (pintype "passive"))
      (node (ref "CN1") (pin "13") (pinfunction "13_13") (pintype "passive"))
      (node (ref "CN1") (pin "16") (pinfunction "16_16") (pintype "passive"))
      (node (ref "CN1") (pin "17") (pinfunction "17_17") (pintype "passive"))
      (node (ref "CN1") (pin "19") (pinfunction "19_19") (pintype "passive"))
      (node (ref "CN1") (pin "20") (pinfunction "20_20") (pintype "passive"))
      (node (ref "CN1") (pin "23") (pinfunction "23_23") (pintype "passive"))
      (node (ref "CN1") (pin "24") (pinfunction "24_24") (pintype "passive"))
      (node (ref "CN1") (pin "28") (pinfunction "28_28") (pintype "passive"))
      (node (ref "CN1") (pin "29") (pinfunction "29_29") (pintype "passive"))
      (node (ref "CN1") (pin "7") (pinfunction "7_7") (pintype "passive"))
      (node (ref "CN1") (pin "8") (pinfunction "8_8") (pintype "passive"))
      (node (ref "D10") (pin "1") (pinfunction "A_1") (pintype "passive"))
      (node (ref "D11") (pin "2") (pinfunction "K_2") (pintype "passive"))
      (node (ref "D12") (pin "2") (pinfunction "K_2") (pintype "passive"))
      (node (ref "D13") (pin "2") (pinfunction "K_2") (pintype "passive"))
      (node (ref "D14") (pin "2") (pinfunction "K_2") (pintype "passive"))
      (node (ref "D15") (pin "1") (pinfunction "A_1") (pintype "passive"))
      (node (ref "D16") (pin "2") (pinfunction "K_2") (pintype "passive"))
      (node (ref "D17") (pin "2") (pinfunction "K_2") (pintype "passive"))
      (node (ref "D18") (pin "2") (pinfunction "K_2") (pintype "passive"))
      (node (ref "D19") (pin "1") (pinfunction "A_1") (pintype "passive"))
      (node (ref "D20") (pin "2") (pinfunction "K_2") (pintype "passive"))
      (node (ref "D21") (pin "2") (pinfunction "K_2") (pintype "passive"))
      (node (ref "D22") (pin "2") (pinfunction "K_2") (pintype "passive"))
      (node (ref "D23") (pin "1") (pinfunction "A_1") (pintype "passive"))
      (node (ref "D24") (pin "2") (pinfunction "K_2") (pintype "passive"))
      (node (ref "D25") (pin "2") (pinfunction "K_2") (pintype "passive"))
      (node (ref "D5") (pin "1") (pinfunction "A_1") (pintype "passive"))
      (node (ref "D8") (pin "2") (pinfunction "K_2") (pintype "passive"))
      (node (ref "D9") (pin "2") (pinfunction "K_2") (pintype "passive"))
      (node (ref "R9") (pin "1") (pinfunction "1_1") (pintype "passive"))
      (node (ref "U2") (pin "5") (pinfunction "Source_5") (pintype "passive"))
      (node (ref "VT1") (pin "3") (pinfunction "3_3") (pintype "passive"))
    )
    (net (code "75") (name "VCC_14V") (class "Default")
      (node (ref "C2") (pin "2") (pinfunction "2_2") (pintype "passive"))
      (node (ref "C3") (pin "1") (pinfunction "1_1") (pintype "passive"))
      (node (ref "C4") (pin "1") (pinfunction "1_1") (pintype "passive"))
      (node (ref "C5") (pin "2") (pinfunction "2_2") (pintype "passive"))
      (node (ref "C6") (pin "2") (pinfunction "2_2") (pintype "passive"))
      (node (ref "C8") (pin "2") (pinfunction "2_2") (pintype "passive"))
      (node (ref "D1") (pin "1") (pinfunction "A_1") (pintype "passive"))
      (node (ref "D2") (pin "1") (pinfunction "A_1") (pintype "passive"))
      (node (ref "D3") (pin "1") (pinfunction "A_1") (pintype "passive"))
      (node (ref "J1") (pin "1") (pinfunction "1_1") (pintype "passive"))
      (node (ref "J2") (pin "1") (pinfunction "1_1") (pintype "passive"))
      (node (ref "J6") (pin "3") (pinfunction "3_3") (pintype "passive"))
      (node (ref "J6") (pin "4") (pinfunction "4_4") (pintype "passive"))
      (node (ref "L1") (pin "2") (pinfunction "2_2") (pintype "passive"))
      (node (ref "Q1") (pin "2") (pinfunction "D_2") (pintype "passive"))
      (node (ref "R2") (pin "2") (pinfunction "2_2") (pintype "passive"))
      (node (ref "U1") (pin "5") (pinfunction "Vcc_5") (pintype "passive"))
      (node (ref "U2") (pin "7") (pinfunction "Vcc_7") (pintype "passive"))
    )
    (net (code "76") (name "unconnected-(1-NC-Pad6)") (class "Default")
      (node (ref "1") (pin "6") (pinfunction "NC_6") (pintype "passive+no_connect"))
    )
    (net (code "77") (name "unconnected-(2-D3-Pad13)") (class "Default")
      (node (ref "2") (pin "13") (pinfunction "D3_13") (pintype "passive"))
    )
    (net (code "78") (name "unconnected-(2-IN2-Pad14)") (class "Default")
      (node (ref "2") (pin "14") (pinfunction "IN2_14") (pintype "passive"))
    )
    (net (code "79") (name "unconnected-(2-NC-Pad6)") (class "Default")
      (node (ref "2") (pin "6") (pinfunction "NC_6") (pintype "passive+no_connect"))
    )
    (net (code "80") (name "unconnected-(2-OUT3-Pad12)") (class "Default")
      (node (ref "2") (pin "12") (pinfunction "OUT3_12") (pintype "passive"))
    )
    (net (code "81") (name "unconnected-(3-NC-Pad6)") (class "Default")
      (node (ref "3") (pin "6") (pinfunction "NC_6") (pintype "passive+no_connect"))
    )
    (net (code "82") (name "unconnected-(4-D4-Pad18)") (class "Default")
      (node (ref "4") (pin "18") (pinfunction "D4_18") (pintype "passive"))
    )
    (net (code "83") (name "unconnected-(4-IN1-Pad17)") (class "Default")
      (node (ref "4") (pin "17") (pinfunction "IN1_17") (pintype "passive"))
    )
    (net (code "84") (name "unconnected-(4-NC-Pad6)") (class "Default")
      (node (ref "4") (pin "6") (pinfunction "NC_6") (pintype "passive+no_connect"))
    )
    (net (code "85") (name "unconnected-(4-OUT4-Pad19)") (class "Default")
      (node (ref "4") (pin "19") (pinfunction "OUT4_19") (pintype "passive"))
    )
    (net (code "86") (name "unconnected-(CN1-Pad31)") (class "Default")
      (node (ref "CN1") (pin "31") (pinfunction "31_31") (pintype "passive+no_connect"))
    )
    (net (code "87") (name "unconnected-(CN1-Pad32)") (class "Default")
      (node (ref "CN1") (pin "32") (pinfunction "32_32") (pintype "passive+no_connect"))
    )
    (net (code "88") (name "unconnected-(J5-Pad1)") (class "Default")
      (node (ref "J5") (pin "1") (pinfunction "1_1") (pintype "passive"))
    )
    (net (code "89") (name "unconnected-(J5-Pad2)") (class "Default")
      (node (ref "J5") (pin "2") (pinfunction "2_2") (pintype "passive"))
    )
    (net (code "90") (name "unconnected-(J6-Pad5)") (class "Default")
      (node (ref "J6") (pin "5") (pinfunction "5_5") (pintype "passive"))
    )
    (net (code "91") (name "unconnected-(J6-Pad6)") (class "Default")
      (node (ref "J6") (pin "6") (pinfunction "6_6") (pintype "passive"))
    )
  )
)
